# MTX_pic_piggyback_V13.net
KiCad netlist of a schematic drawn in EAGLE
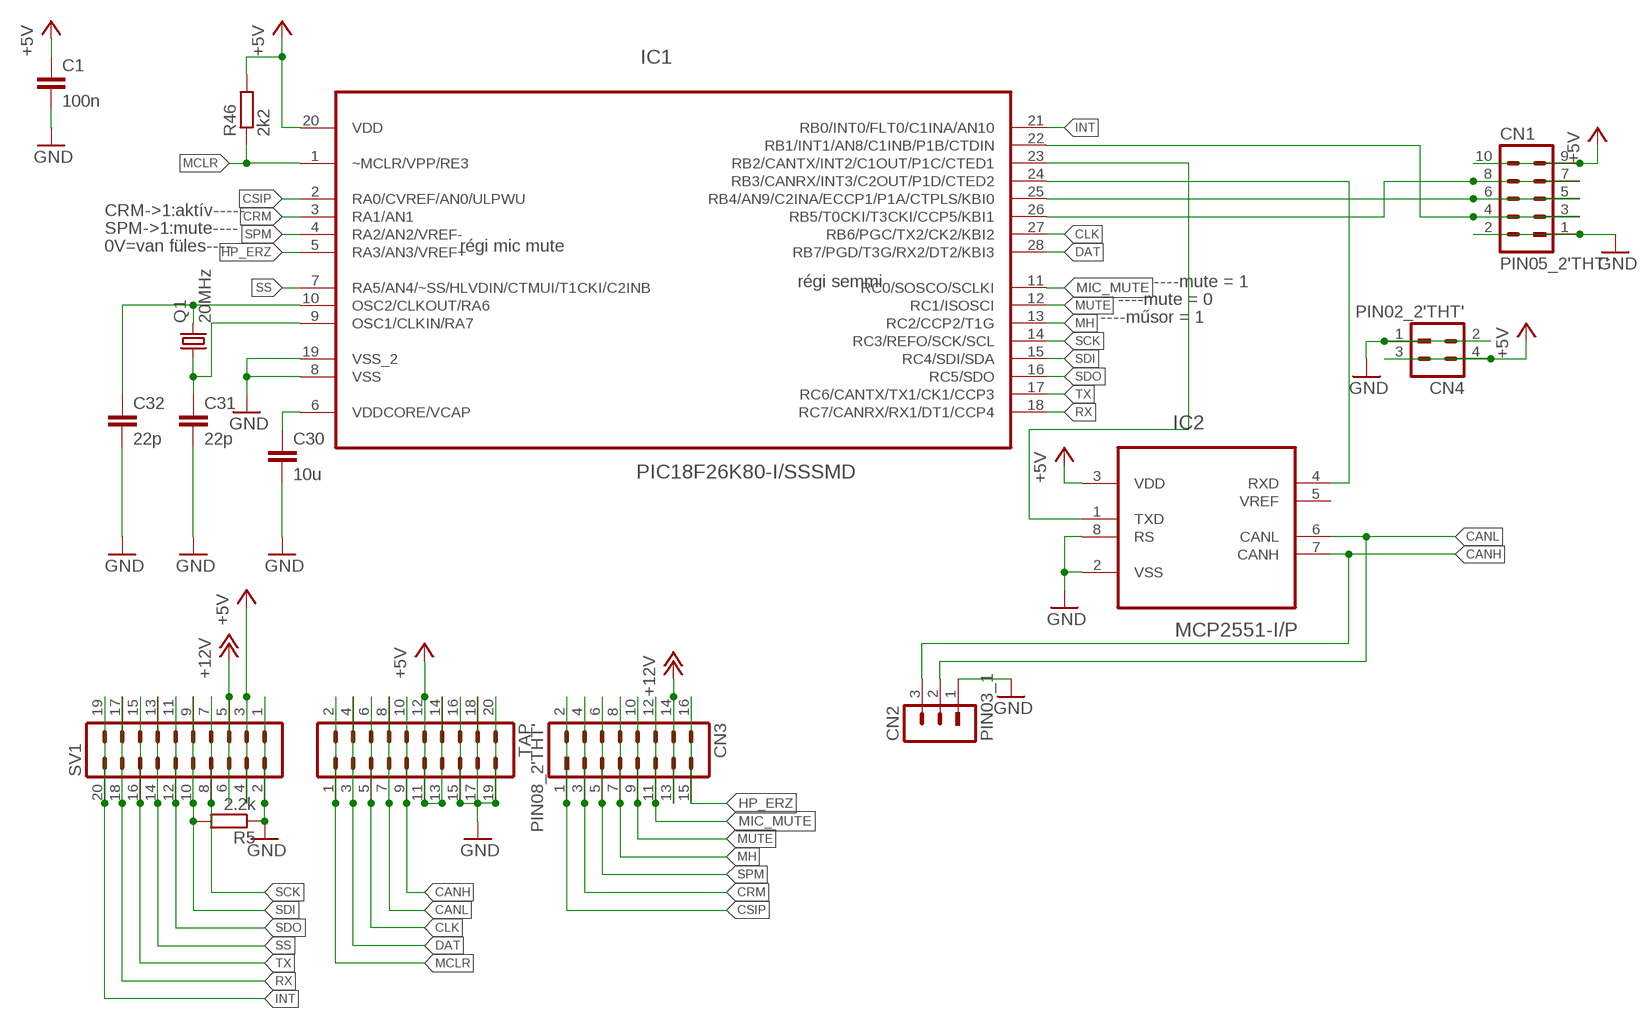
[diagram p0: schematic, sheet 1]

(export (version "E")
  (design (tool "Eeschema 10.0.6"))
  (components
    (comp (ref "C1")
      (value "100n")
      (footprint "eagle-import:C0805")
      (libsource (lib "eagle-import") (part "C-EUC0805"))
    )
    (comp (ref "C30")
      (value "10u")
      (footprint "eagle-import:C0805")
      (libsource (lib "eagle-import") (part "C-EUC0805"))
    )
    (comp (ref "C31")
      (value "22p")
      (footprint "eagle-import:C0805")
      (libsource (lib "eagle-import") (part "C-EUC0805"))
    )
    (comp (ref "C32")
      (value "22p")
      (footprint "eagle-import:C0805")
      (libsource (lib "eagle-import") (part "C-EUC0805"))
    )
    (comp (ref "CN1")
      (value "PIN05_2'THT'")
      (footprint "eagle-import:PIN05_2")
      (libsource (lib "eagle-import") (part "PIN05_2'THT'"))
    )
    (comp (ref "CN2")
      (value "PIN03_1")
      (footprint "eagle-import:PIN03_1")
      (libsource (lib "eagle-import") (part "PIN03_1"))
    )
    (comp (ref "CN3")
      (value "PIN08_2'THT'")
      (footprint "eagle-import:PIN08_2")
      (libsource (lib "eagle-import") (part "PIN08_2'THT'"))
    )
    (comp (ref "CN4")
      (value "PIN02_2'THT'")
      (footprint "eagle-import:PIN02_2")
      (libsource (lib "eagle-import") (part "PIN02_2'THT'"))
    )
    (comp (ref "IC1")
      (value "PIC18F26K80-I/SSSMD")
      (footprint "eagle-import:SOP65P780X200-28N")
      (libsource (lib "eagle-import") (part "PIC18F25K80-I/SSSMD"))
    )
    (comp (ref "IC2")
      (value "MCP2551-I/P")
      (footprint "eagle-import:DIP254P762X432-8")
      (libsource (lib "eagle-import") (part "MCP2551-I/P"))
    )
    (comp (ref "Q1")
      (value "20MHz")
      (footprint "eagle-import:XTAL_QS")
      (libsource (lib "eagle-import") (part "XTAL_2QS"))
    )
    (comp (ref "R5")
      (value "2.2k")
      (footprint "eagle-import:R0805")
      (libsource (lib "eagle-import") (part "R-EU_R0805"))
    )
    (comp (ref "R46")
      (value "2k2")
      (footprint "eagle-import:R0805")
      (libsource (lib "eagle-import") (part "R-EU_R0805"))
    )
    (comp (ref "SV1")
      (value "MA10-2")
      (footprint "eagle-import:MA10-2")
      (libsource (lib "eagle-import") (part "MA10-2"))
    )
    (comp (ref "TAP")
      (value "MA10-2")
      (footprint "eagle-import:MA10-2")
      (libsource (lib "eagle-import") (part "MA10-2"))
    )
  )
  (nets
    (net (code "1") (name "+5V") (class "Default")
      (node (ref "C1") (pin "1") (pinfunction "1_1") (pintype "passive"))
      (node (ref "CN1") (pin "10") (pinfunction "10_10") (pintype "passive"))
      (node (ref "CN1") (pin "9") (pinfunction "9_9") (pintype "passive"))
      (node (ref "CN4") (pin "3") (pinfunction "3_3") (pintype "passive"))
      (node (ref "CN4") (pin "4") (pinfunction "4_4") (pintype "passive"))
      (node (ref "IC1") (pin "20") (pinfunction "VDD_20") (pintype "power_in"))
      (node (ref "IC2") (pin "3") (pinfunction "VDD_3") (pintype "power_in"))
      (node (ref "R46") (pin "2") (pinfunction "2_2") (pintype "passive"))
      (node (ref "SV1") (pin "3") (pinfunction "3_3") (pintype "passive"))
      (node (ref "SV1") (pin "4") (pinfunction "4_4") (pintype "passive"))
      (node (ref "TAP") (pin "11") (pinfunction "11_11") (pintype "passive"))
      (node (ref "TAP") (pin "12") (pinfunction "12_12") (pintype "passive"))
      (node (ref "TAP") (pin "13") (pinfunction "13_13") (pintype "passive"))
      (node (ref "TAP") (pin "14") (pinfunction "14_14") (pintype "passive"))
    )
    (net (code "2") (name "+12V") (class "Default")
      (node (ref "CN3") (pin "13") (pinfunction "13_13") (pintype "passive"))
      (node (ref "CN3") (pin "14") (pinfunction "14_14") (pintype "passive"))
      (node (ref "SV1") (pin "5") (pinfunction "5_5") (pintype "passive"))
      (node (ref "SV1") (pin "6") (pinfunction "6_6") (pintype "passive"))
    )
    (net (code "3") (name "CANH") (class "Default")
      (node (ref "CN2") (pin "3") (pinfunction "3_3") (pintype "passive"))
      (node (ref "IC2") (pin "7") (pinfunction "CANH_7") (pintype "bidirectional"))
      (node (ref "TAP") (pin "10") (pinfunction "10_10") (pintype "passive"))
      (node (ref "TAP") (pin "9") (pinfunction "9_9") (pintype "passive"))
    )
    (net (code "4") (name "CANL") (class "Default")
      (node (ref "CN2") (pin "2") (pinfunction "2_2") (pintype "passive"))
      (node (ref "IC2") (pin "6") (pinfunction "CANL_6") (pintype "bidirectional"))
      (node (ref "TAP") (pin "7") (pinfunction "7_7") (pintype "passive"))
      (node (ref "TAP") (pin "8") (pinfunction "8_8") (pintype "passive"))
    )
    (net (code "5") (name "CLK") (class "Default")
      (node (ref "IC1") (pin "27") (pinfunction "RB6/PGC/TX2/CK2/KBI2_27") (pintype "bidirectional"))
      (node (ref "TAP") (pin "5") (pinfunction "5_5") (pintype "passive"))
      (node (ref "TAP") (pin "6") (pinfunction "6_6") (pintype "passive"))
    )
    (net (code "6") (name "CRM") (class "Default")
      (node (ref "CN3") (pin "3") (pinfunction "3_3") (pintype "passive"))
      (node (ref "CN3") (pin "4") (pinfunction "4_4") (pintype "passive"))
      (node (ref "IC1") (pin "3") (pinfunction "RA1/AN1_3") (pintype "bidirectional"))
    )
    (net (code "7") (name "CSIP") (class "Default")
      (node (ref "CN3") (pin "1") (pinfunction "1_1") (pintype "passive"))
      (node (ref "CN3") (pin "2") (pinfunction "2_2") (pintype "passive"))
      (node (ref "IC1") (pin "2") (pinfunction "RA0/CVREF/AN0/ULPWU_2") (pintype "bidirectional"))
    )
    (net (code "8") (name "DAT") (class "Default")
      (node (ref "IC1") (pin "28") (pinfunction "RB7/PGD/T3G/RX2/DT2/KBI3_28") (pintype "bidirectional"))
      (node (ref "TAP") (pin "3") (pinfunction "3_3") (pintype "passive"))
      (node (ref "TAP") (pin "4") (pinfunction "4_4") (pintype "passive"))
    )
    (net (code "9") (name "GND") (class "Default")
      (node (ref "C1") (pin "2") (pinfunction "2_2") (pintype "passive"))
      (node (ref "C30") (pin "2") (pinfunction "2_2") (pintype "passive"))
      (node (ref "C31") (pin "2") (pinfunction "2_2") (pintype "passive"))
      (node (ref "C32") (pin "2") (pinfunction "2_2") (pintype "passive"))
      (node (ref "CN1") (pin "1") (pinfunction "1_1") (pintype "passive"))
      (node (ref "CN1") (pin "2") (pinfunction "2_2") (pintype "passive"))
      (node (ref "CN2") (pin "1") (pinfunction "1_1") (pintype "passive"))
      (node (ref "CN4") (pin "1") (pinfunction "1_1") (pintype "passive"))
      (node (ref "CN4") (pin "2") (pinfunction "2_2") (pintype "passive"))
      (node (ref "IC1") (pin "19") (pinfunction "VSS_2_19") (pintype "power_in"))
      (node (ref "IC1") (pin "8") (pinfunction "VSS_8") (pintype "power_in"))
      (node (ref "IC2") (pin "2") (pinfunction "VSS_2") (pintype "power_in"))
      (node (ref "IC2") (pin "8") (pinfunction "RS_8") (pintype "input"))
      (node (ref "R5") (pin "1") (pinfunction "1_1") (pintype "passive"))
      (node (ref "SV1") (pin "1") (pinfunction "1_1") (pintype "passive"))
      (node (ref "SV1") (pin "2") (pinfunction "2_2") (pintype "passive"))
      (node (ref "TAP") (pin "15") (pinfunction "15_15") (pintype "passive"))
      (node (ref "TAP") (pin "16") (pinfunction "16_16") (pintype "passive"))
      (node (ref "TAP") (pin "17") (pinfunction "17_17") (pintype "passive"))
      (node (ref "TAP") (pin "18") (pinfunction "18_18") (pintype "passive"))
      (node (ref "TAP") (pin "19") (pinfunction "19_19") (pintype "passive"))
      (node (ref "TAP") (pin "20") (pinfunction "20_20") (pintype "passive"))
    )
    (net (code "10") (name "HP_ERZ") (class "Default")
      (node (ref "CN3") (pin "15") (pinfunction "15_15") (pintype "passive"))
      (node (ref "CN3") (pin "16") (pinfunction "16_16") (pintype "passive"))
      (node (ref "IC1") (pin "5") (pinfunction "RA3/AN3/VREF+_5") (pintype "bidirectional"))
    )
    (net (code "11") (name "INT") (class "Default")
      (node (ref "IC1") (pin "21") (pinfunction "RB0/INT0/FLT0/C1INA/AN10_21") (pintype "bidirectional"))
      (node (ref "SV1") (pin "19") (pinfunction "19_19") (pintype "passive"))
      (node (ref "SV1") (pin "20") (pinfunction "20_20") (pintype "passive"))
    )
    (net (code "12") (name "MCLR") (class "Default")
      (node (ref "IC1") (pin "1") (pinfunction "~{MCLR/VPP/RE3}_1") (pintype "input"))
      (node (ref "R46") (pin "1") (pinfunction "1_1") (pintype "passive"))
      (node (ref "TAP") (pin "1") (pinfunction "1_1") (pintype "passive"))
      (node (ref "TAP") (pin "2") (pinfunction "2_2") (pintype "passive"))
    )
    (net (code "13") (name "MH") (class "Default")
      (node (ref "CN3") (pin "7") (pinfunction "7_7") (pintype "passive"))
      (node (ref "CN3") (pin "8") (pinfunction "8_8") (pintype "passive"))
      (node (ref "IC1") (pin "13") (pinfunction "RC2/CCP2/T1G_13") (pintype "bidirectional"))
    )
    (net (code "14") (name "MIC_MUTE") (class "Default")
      (node (ref "CN3") (pin "11") (pinfunction "11_11") (pintype "passive"))
      (node (ref "CN3") (pin "12") (pinfunction "12_12") (pintype "passive"))
      (node (ref "IC1") (pin "11") (pinfunction "RC0/SOSCO/SCLKI_11") (pintype "bidirectional"))
    )
    (net (code "15") (name "MUTE") (class "Default")
      (node (ref "CN3") (pin "10") (pinfunction "10_10") (pintype "passive"))
      (node (ref "CN3") (pin "9") (pinfunction "9_9") (pintype "passive"))
      (node (ref "IC1") (pin "12") (pinfunction "RC1/ISOSCI_12") (pintype "bidirectional"))
    )
    (net (code "16") (name "Net-(IC1-OSC1{slash}CLKIN{slash}RA7)") (class "Default")
      (node (ref "C31") (pin "1") (pinfunction "1_1") (pintype "passive"))
      (node (ref "IC1") (pin "9") (pinfunction "OSC1/CLKIN/RA7_9") (pintype "bidirectional"))
      (node (ref "Q1") (pin "1") (pinfunction "1_1") (pintype "passive"))
    )
    (net (code "17") (name "Net-(IC1-OSC2{slash}CLKOUT{slash}RA6)") (class "Default")
      (node (ref "C32") (pin "1") (pinfunction "1_1") (pintype "passive"))
      (node (ref "IC1") (pin "10") (pinfunction "OSC2/CLKOUT/RA6_10") (pintype "bidirectional"))
      (node (ref "Q1") (pin "2") (pinfunction "2_2") (pintype "passive"))
    )
    (net (code "18") (name "Net-(IC1-RB1{slash}INT1{slash}AN8{slash}C1INB{slash}P1B{slash}CTDIN)") (class "Default")
      (node (ref "CN1") (pin "3") (pinfunction "3_3") (pintype "passive"))
      (node (ref "CN1") (pin "4") (pinfunction "4_4") (pintype "passive"))
      (node (ref "IC1") (pin "22") (pinfunction "RB1/INT1/AN8/C1INB/P1B/CTDIN_22") (pintype "bidirectional"))
    )
    (net (code "19") (name "Net-(IC1-RB2{slash}CANTX{slash}INT2{slash}C1OUT{slash}P1C{slash}CTED1)") (class "Default")
      (node (ref "IC1") (pin "23") (pinfunction "RB2/CANTX/INT2/C1OUT/P1C/CTED1_23") (pintype "bidirectional"))
      (node (ref "IC2") (pin "1") (pinfunction "TXD_1") (pintype "input"))
    )
    (net (code "20") (name "Net-(IC1-RB3{slash}CANRX{slash}INT3{slash}C2OUT{slash}P1D{slash}CTED2)") (class "Default")
      (node (ref "IC1") (pin "24") (pinfunction "RB3/CANRX/INT3/C2OUT/P1D/CTED2_24") (pintype "bidirectional"))
      (node (ref "IC2") (pin "4") (pinfunction "RXD_4") (pintype "output"))
    )
    (net (code "21") (name "Net-(IC1-RB4{slash}AN9{slash}C2INA{slash}ECCP1{slash}P1A{slash}CTPLS{slash}KBI0)") (class "Default")
      (node (ref "CN1") (pin "5") (pinfunction "5_5") (pintype "passive"))
      (node (ref "CN1") (pin "6") (pinfunction "6_6") (pintype "passive"))
      (node (ref "IC1") (pin "25") (pinfunction "RB4/AN9/C2INA/ECCP1/P1A/CTPLS/KBI0_25") (pintype "bidirectional"))
    )
    (net (code "22") (name "Net-(IC1-RB5{slash}T0CKI{slash}T3CKI{slash}CCP5{slash}KBI1)") (class "Default")
      (node (ref "CN1") (pin "7") (pinfunction "7_7") (pintype "passive"))
      (node (ref "CN1") (pin "8") (pinfunction "8_8") (pintype "passive"))
      (node (ref "IC1") (pin "26") (pinfunction "RB5/T0CKI/T3CKI/CCP5/KBI1_26") (pintype "bidirectional"))
    )
    (net (code "23") (name "Net-(IC1-VDDCORE{slash}VCAP)") (class "Default")
      (node (ref "C30") (pin "1") (pinfunction "1_1") (pintype "passive"))
      (node (ref "IC1") (pin "6") (pinfunction "VDDCORE/VCAP_6") (pintype "bidirectional"))
    )
    (net (code "24") (name "RX") (class "Default")
      (node (ref "IC1") (pin "18") (pinfunction "RC7/CANRX/RX1/DT1/CCP4_18") (pintype "bidirectional"))
      (node (ref "SV1") (pin "17") (pinfunction "17_17") (pintype "passive"))
      (node (ref "SV1") (pin "18") (pinfunction "18_18") (pintype "passive"))
    )
    (net (code "25") (name "SCK") (class "Default")
      (node (ref "IC1") (pin "14") (pinfunction "RC3/REFO/SCK/SCL_14") (pintype "bidirectional"))
      (node (ref "SV1") (pin "7") (pinfunction "7_7") (pintype "passive"))
      (node (ref "SV1") (pin "8") (pinfunction "8_8") (pintype "passive"))
    )
    (net (code "26") (name "SDI") (class "Default")
      (node (ref "IC1") (pin "15") (pinfunction "RC4/SDI/SDA_15") (pintype "bidirectional"))
      (node (ref "R5") (pin "2") (pinfunction "2_2") (pintype "passive"))
      (node (ref "SV1") (pin "10") (pinfunction "10_10") (pintype "passive"))
      (node (ref "SV1") (pin "9") (pinfunction "9_9") (pintype "passive"))
    )
    (net (code "27") (name "SDO") (class "Default")
      (node (ref "IC1") (pin "16") (pinfunction "RC5/SDO_16") (pintype "bidirectional"))
      (node (ref "SV1") (pin "11") (pinfunction "11_11") (pintype "passive"))
      (node (ref "SV1") (pin "12") (pinfunction "12_12") (pintype "passive"))
    )
    (net (code "28") (name "SPM") (class "Default")
      (node (ref "CN3") (pin "5") (pinfunction "5_5") (pintype "passive"))
      (node (ref "CN3") (pin "6") (pinfunction "6_6") (pintype "passive"))
      (node (ref "IC1") (pin "4") (pinfunction "RA2/AN2/VREF-_4") (pintype "bidirectional"))
    )
    (net (code "29") (name "SS") (class "Default")
      (node (ref "IC1") (pin "7") (pinfunction "RA5/AN4/~{SS/HLVDIN/CTMUI/T1CKI/C2INB}_7") (pintype "bidirectional"))
      (node (ref "SV1") (pin "13") (pinfunction "13_13") (pintype "passive"))
      (node (ref "SV1") (pin "14") (pinfunction "14_14") (pintype "passive"))
    )
    (net (code "30") (name "TX") (class "Default")
      (node (ref "IC1") (pin "17") (pinfunction "RC6/CANTX/TX1/CK1/CCP3_17") (pintype "bidirectional"))
      (node (ref "SV1") (pin "15") (pinfunction "15_15") (pintype "passive"))
      (node (ref "SV1") (pin "16") (pinfunction "16_16") (pintype "passive"))
    )
    (net (code "31") (name "unconnected-(IC2-VREF-Pad5)") (class "Default")
      (node (ref "IC2") (pin "5") (pinfunction "VREF_5") (pintype "output"))
    )
  )
)
